# Indicators.net
KiCad netlist of a schematic drawn in Altium Designer
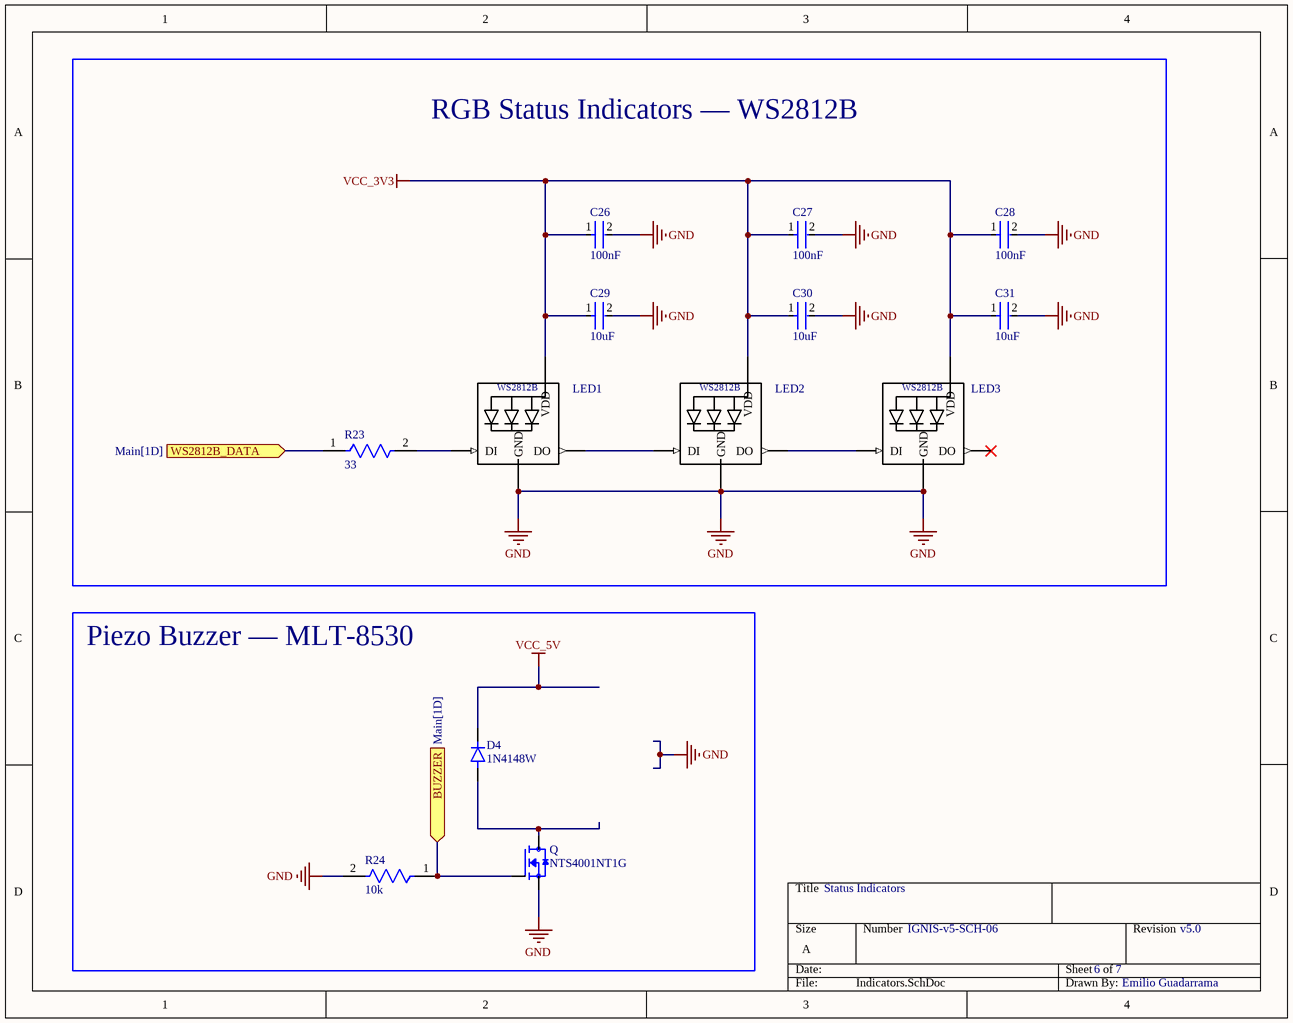
[diagram p0: Indicators.SchDoc]

(export (version "E")
  (design (tool "Eeschema 10.0.6"))
  (components
    (comp (ref "C26")
      (value "100nF")
      (footprint "FP-C0805C-DN-MFG")
      (description "CAP CER 0.1UF 50V X7R 0805")
      (fields
        (field (name "MANUFACTURER PART NUMBER") "C0805C104K5RACTU")
        (field (name "MANUFACTURER") "KEMET")
      )
      (libsource (lib "Altium Content Vault") (part "b4654b650e69147ec39a6b967a45e02"))
    )
    (comp (ref "C27")
      (value "100nF")
      (footprint "FP-C0805C-DN-MFG")
      (description "CAP CER 0.1UF 50V X7R 0805")
      (fields
        (field (name "MANUFACTURER PART NUMBER") "C0805C104K5RACTU")
        (field (name "MANUFACTURER") "KEMET")
      )
      (libsource (lib "Altium Content Vault") (part "b4654b650e69147ec39a6b967a45e02"))
    )
    (comp (ref "C28")
      (value "100nF")
      (footprint "FP-C0805C-DN-MFG")
      (description "CAP CER 0.1UF 50V X7R 0805")
      (fields
        (field (name "MANUFACTURER PART NUMBER") "C0805C104K5RACTU")
        (field (name "MANUFACTURER") "KEMET")
      )
      (libsource (lib "Altium Content Vault") (part "b4654b650e69147ec39a6b967a45e02"))
    )
    (comp (ref "C29")
      (value "10uF")
      (footprint "FP-C0805C-DN-MFG")
      (description "CAP CER 0.1UF 50V X7R 0805")
      (fields
        (field (name "MANUFACTURER PART NUMBER") "C0805C104K5RACTU")
        (field (name "MANUFACTURER") "KEMET")
      )
      (libsource (lib "Altium Content Vault") (part "b4654b650e69147ec39a6b967a45e02"))
    )
    (comp (ref "C30")
      (value "10uF")
      (footprint "FP-C0805C-DN-MFG")
      (description "CAP CER 0.1UF 50V X7R 0805")
      (fields
        (field (name "MANUFACTURER PART NUMBER") "C0805C104K5RACTU")
        (field (name "MANUFACTURER") "KEMET")
      )
      (libsource (lib "Altium Content Vault") (part "b4654b650e69147ec39a6b967a45e02"))
    )
    (comp (ref "C31")
      (value "10uF")
      (footprint "FP-C0805C-DN-MFG")
      (description "CAP CER 0.1UF 50V X7R 0805")
      (fields
        (field (name "MANUFACTURER PART NUMBER") "C0805C104K5RACTU")
        (field (name "MANUFACTURER") "KEMET")
      )
      (libsource (lib "Altium Content Vault") (part "b4654b650e69147ec39a6b967a45e02"))
    )
    (comp (ref "D4")
      (value "1N4148W")
      (footprint "SODFL3816X120N")
      (description "Small Signal Diode, SOD-123F, 100V, 0.15A, 150Â°C")
      (fields (field (name "MF") "Diotec Semiconductor"))
      (libsource (lib "1N4148W") (part "1N4148W"))
    )
    (comp (ref "LED1")
      (value "WS2812B")
      (footprint "*LED3535")
      (description "Intelligent control LED integrated light source")
      (fields (field (name "MF") "Worldsemi"))
      (libsource (lib "LED_RGB_WS2812B") (part "WS2812B"))
    )
    (comp (ref "LED2")
      (value "WS2812B")
      (footprint "*LED3535")
      (description "Intelligent control LED integrated light source")
      (fields (field (name "MF") "Worldsemi"))
      (libsource (lib "LED_RGB_WS2812B") (part "WS2812B"))
    )
    (comp (ref "LED3")
      (value "WS2812B")
      (footprint "*LED3535")
      (description "Intelligent control LED integrated light source")
      (fields (field (name "MF") "Worldsemi"))
      (libsource (lib "LED_RGB_WS2812B") (part "WS2812B"))
    )
    (comp (ref "Q")
      (value "NTS4001NT1G")
      (footprint "SOT65P220X100-3N")
      (description "N-Channel 30V 270mA _Ta_ 330mW _Ta_ Surface Mount SC-70-3 _SOT323_")
      (fields (field (name "MF") "ON Semiconductor"))
      (libsource (lib "NTS4001NT1G") (part "NTS4001NT1G"))
    )
    (comp (ref "R23")
      (value "33")
      (footprint "FP-MCT0603-IPC_A")
      (description "RES SMD 100 OHM 1% 1/8W 0603")
      (fields (field (name "TOLERANCE") "0.1%"))
      (libsource (lib "Altium Content Vault") (part "1029c3af85768c4190bb7ad29bc67b5"))
    )
    (comp (ref "R24")
      (value "10k")
      (footprint "FP-MCT0603-IPC_A")
      (description "RES SMD 100 OHM 1% 1/8W 0603")
      (fields (field (name "TOLERANCE") "0.1%"))
      (libsource (lib "Altium Content Vault") (part "1029c3af85768c4190bb7ad29bc67b5"))
    )
  )
  (nets
    (net (code "1") (name "/BUZZER") (class "Default")
      (node (ref "Q") (pin "1") (pinfunction "G_1") (pintype "passive"))
      (node (ref "R24") (pin "1") (pinfunction "1_1") (pintype "passive"))
    )
    (net (code "2") (name "/WS2812B_DATA") (class "Default")
      (node (ref "R23") (pin "1") (pinfunction "1_1") (pintype "passive"))
    )
    (net (code "3") (name "GND") (class "Default")
      (node (ref "C26") (pin "2") (pinfunction "2_2") (pintype "passive"))
      (node (ref "C27") (pin "2") (pinfunction "2_2") (pintype "passive"))
      (node (ref "C28") (pin "2") (pinfunction "2_2") (pintype "passive"))
      (node (ref "C29") (pin "2") (pinfunction "2_2") (pintype "passive"))
      (node (ref "C30") (pin "2") (pinfunction "2_2") (pintype "passive"))
      (node (ref "C31") (pin "2") (pinfunction "2_2") (pintype "passive"))
      (node (ref "LED1") (pin "3") (pinfunction "GND_3") (pintype "power_in"))
      (node (ref "LED2") (pin "3") (pinfunction "GND_3") (pintype "power_in"))
      (node (ref "LED3") (pin "3") (pinfunction "GND_3") (pintype "power_in"))
      (node (ref "Q") (pin "2") (pinfunction "S_2") (pintype "passive"))
      (node (ref "R24") (pin "2") (pinfunction "2_2") (pintype "passive"))
    )
    (net (code "4") (name "Net-(LED1-DI)") (class "Default")
      (node (ref "LED1") (pin "4") (pinfunction "DI_4") (pintype "input"))
      (node (ref "R23") (pin "2") (pinfunction "2_2") (pintype "passive"))
    )
    (net (code "5") (name "Net-(LED1-DO)") (class "Default")
      (node (ref "LED1") (pin "2") (pinfunction "DO_2") (pintype "output"))
      (node (ref "LED2") (pin "4") (pinfunction "DI_4") (pintype "input"))
    )
    (net (code "6") (name "Net-(LED2-DO)") (class "Default")
      (node (ref "LED2") (pin "2") (pinfunction "DO_2") (pintype "output"))
      (node (ref "LED3") (pin "4") (pinfunction "DI_4") (pintype "input"))
    )
    (net (code "7") (name "Net-(Q-D)") (class "Default")
      (node (ref "D4") (pin "A") (pinfunction "A_A") (pintype "passive"))
      (node (ref "Q") (pin "3") (pinfunction "D_3") (pintype "passive"))
    )
    (net (code "8") (name "VCC_3V3") (class "Default")
      (node (ref "C26") (pin "1") (pinfunction "1_1") (pintype "passive"))
      (node (ref "C27") (pin "1") (pinfunction "1_1") (pintype "passive"))
      (node (ref "C28") (pin "1") (pinfunction "1_1") (pintype "passive"))
      (node (ref "C29") (pin "1") (pinfunction "1_1") (pintype "passive"))
      (node (ref "C30") (pin "1") (pinfunction "1_1") (pintype "passive"))
      (node (ref "C31") (pin "1") (pinfunction "1_1") (pintype "passive"))
      (node (ref "LED1") (pin "1") (pinfunction "VDD_1") (pintype "power_in"))
      (node (ref "LED2") (pin "1") (pinfunction "VDD_1") (pintype "power_in"))
      (node (ref "LED3") (pin "1") (pinfunction "VDD_1") (pintype "power_in"))
    )
    (net (code "9") (name "VCC_5V") (class "Default")
      (node (ref "D4") (pin "C") (pinfunction "K_C") (pintype "passive"))
    )
    (net (code "10") (name "unconnected-(LED3-DO-Pad2)") (class "Default")
      (node (ref "LED3") (pin "2") (pinfunction "DO_2") (pintype "output+no_connect"))
    )
  )
)
